# SCH_USBHubMME_2025-02-13.net
KiCad netlist of a schematic drawn in EasyEDA
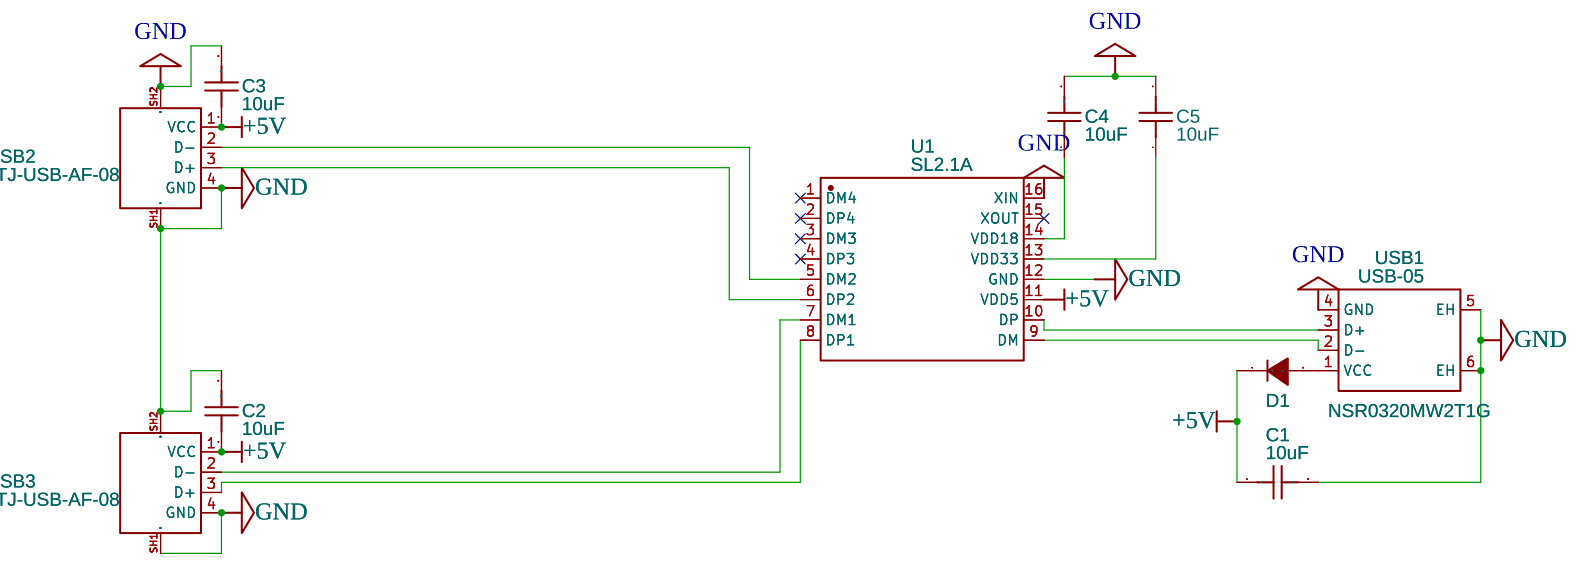
[diagram p0: schematic sheet]

(export (version "E")
  (design (tool "Eeschema 10.0.6"))
  (components
    (comp (ref "C1")
      (value "10uF")
      (fields
        (field (name "Manufacturer Part") "CL10A106KP8NNNC")
        (field (name "Manufacturer") "SAMSUNG(三星)")
      )
      (libsource (lib "") (part "CL10A106KP8NNNC"))
    )
    (comp (ref "C2")
      (value "10uF")
      (fields
        (field (name "Manufacturer Part") "CL10A106KP8NNNC")
        (field (name "Manufacturer") "SAMSUNG(三星)")
      )
      (libsource (lib "") (part "CL10A106KP8NNNC_1"))
    )
    (comp (ref "C3")
      (value "10uF")
      (fields
        (field (name "Manufacturer Part") "CL10A106KP8NNNC")
        (field (name "Manufacturer") "SAMSUNG(三星)")
      )
      (libsource (lib "") (part "CL10A106KP8NNNC_1"))
    )
    (comp (ref "C4")
      (value "10uF")
      (fields
        (field (name "Manufacturer Part") "CL10A106KP8NNNC")
        (field (name "Manufacturer") "SAMSUNG(三星)")
      )
      (libsource (lib "") (part "CL10A106KP8NNNC_1"))
    )
    (comp (ref "C5")
      (value "10uF")
      (fields
        (field (name "Manufacturer Part") "CL10A106KP8NNNC")
        (field (name "Manufacturer") "SAMSUNG(三星)")
      )
      (libsource (lib "") (part "CL10A106KP8NNNC_1"))
    )
    (comp (ref "D1")
      (value "NSR0320MW2T1G")
      (fields (field (name "Manufacturer") "onsemi(安森美)"))
      (libsource (lib "") (part "NSR0320MW2T1G"))
    )
    (comp (ref "U1")
      (value "SL2.1A")
      (fields (field (name "Manufacturer") "CoreChips(和芯润德)"))
      (libsource (lib "") (part "SL2.1A"))
    )
    (comp (ref "USB1")
      (value "USB-05")
      (fields (field (name "Manufacturer") "SOFNG(硕方)"))
      (libsource (lib "") (part "USB-05"))
    )
    (comp (ref "USB2")
      (value "JTJ-USB-AF-08")
      (fields (field (name "Manufacturer Part") "902-131A1011D10100") (field (name "Manufacturer") "精拓金"))
      (libsource (lib "") (part "JTJ-USB-AF-08"))
    )
    (comp (ref "USB3")
      (value "JTJ-USB-AF-08")
      (fields (field (name "Manufacturer Part") "902-131A1011D10100") (field (name "Manufacturer") "精拓金"))
      (libsource (lib "") (part "JTJ-USB-AF-08"))
    )
  )
  (nets
    (net (code "1") (name "+5V") (class "Default")
      (node (ref "C1") (pin "1") (pinfunction "1_1") (pintype "unspecified"))
      (node (ref "C2") (pin "1") (pinfunction "1_1") (pintype "unspecified"))
      (node (ref "C3") (pin "1") (pinfunction "1_1") (pintype "unspecified"))
      (node (ref "D1") (pin "1") (pinfunction "C_1") (pintype "unspecified"))
      (node (ref "U1") (pin "11") (pinfunction "VDD5_11") (pintype "unspecified"))
      (node (ref "USB2") (pin "1") (pinfunction "VCC_1") (pintype "input"))
      (node (ref "USB3") (pin "1") (pinfunction "VCC_1") (pintype "input"))
    )
    (net (code "2") (name "GND") (class "Default")
      (node (ref "C1") (pin "2") (pinfunction "2_2") (pintype "unspecified"))
      (node (ref "C2") (pin "2") (pinfunction "2_2") (pintype "unspecified"))
      (node (ref "C3") (pin "2") (pinfunction "2_2") (pintype "unspecified"))
      (node (ref "C4") (pin "2") (pinfunction "2_2") (pintype "unspecified"))
      (node (ref "C5") (pin "2") (pinfunction "2_2") (pintype "unspecified"))
      (node (ref "U1") (pin "12") (pinfunction "GND_12") (pintype "unspecified"))
      (node (ref "U1") (pin "16") (pinfunction "XIN_16") (pintype "unspecified"))
      (node (ref "USB1") (pin "4") (pinfunction "GND_4") (pintype "input"))
      (node (ref "USB1") (pin "5") (pinfunction "EH_5") (pintype "unspecified"))
      (node (ref "USB1") (pin "6") (pinfunction "EH_6") (pintype "unspecified"))
      (node (ref "USB2") (pin "4") (pinfunction "GND_4") (pintype "input"))
      (node (ref "USB2") (pin "SH1") (pinfunction "SH1_SH1") (pintype "unspecified"))
      (node (ref "USB2") (pin "SH2") (pinfunction "SH2_SH2") (pintype "unspecified"))
      (node (ref "USB3") (pin "4") (pinfunction "GND_4") (pintype "input"))
      (node (ref "USB3") (pin "SH1") (pinfunction "SH1_SH1") (pintype "unspecified"))
      (node (ref "USB3") (pin "SH2") (pinfunction "SH2_SH2") (pintype "unspecified"))
    )
    (net (code "3") (name "Net-(D1-A)") (class "Default")
      (node (ref "D1") (pin "2") (pinfunction "A_2") (pintype "unspecified"))
      (node (ref "USB1") (pin "1") (pinfunction "VCC_1") (pintype "input"))
    )
    (net (code "4") (name "Net-(U1-DM)") (class "Default")
      (node (ref "U1") (pin "9") (pinfunction "DM_9") (pintype "unspecified"))
      (node (ref "USB1") (pin "2") (pinfunction "D-_2") (pintype "input"))
    )
    (net (code "5") (name "Net-(U1-DM1)") (class "Default")
      (node (ref "U1") (pin "7") (pinfunction "DM1_7") (pintype "unspecified"))
      (node (ref "USB3") (pin "2") (pinfunction "D-_2") (pintype "input"))
    )
    (net (code "6") (name "Net-(U1-DM2)") (class "Default")
      (node (ref "U1") (pin "5") (pinfunction "DM2_5") (pintype "unspecified"))
      (node (ref "USB2") (pin "2") (pinfunction "D-_2") (pintype "input"))
    )
    (net (code "7") (name "Net-(U1-DP)") (class "Default")
      (node (ref "U1") (pin "10") (pinfunction "DP_10") (pintype "unspecified"))
      (node (ref "USB1") (pin "3") (pinfunction "D+_3") (pintype "input"))
    )
    (net (code "8") (name "Net-(U1-DP1)") (class "Default")
      (node (ref "U1") (pin "8") (pinfunction "DP1_8") (pintype "unspecified"))
      (node (ref "USB3") (pin "3") (pinfunction "D+_3") (pintype "input"))
    )
    (net (code "9") (name "Net-(U1-DP2)") (class "Default")
      (node (ref "U1") (pin "6") (pinfunction "DP2_6") (pintype "unspecified"))
      (node (ref "USB2") (pin "3") (pinfunction "D+_3") (pintype "input"))
    )
    (net (code "10") (name "Net-(U1-VDD18)") (class "Default")
      (node (ref "C4") (pin "1") (pinfunction "1_1") (pintype "unspecified"))
      (node (ref "U1") (pin "14") (pinfunction "VDD18_14") (pintype "unspecified"))
    )
    (net (code "11") (name "Net-(U1-VDD33)") (class "Default")
      (node (ref "C5") (pin "1") (pinfunction "1_1") (pintype "unspecified"))
      (node (ref "U1") (pin "13") (pinfunction "VDD33_13") (pintype "unspecified"))
    )
    (net (code "12") (name "unconnected-(U1-DM3-Pad3)") (class "Default")
      (node (ref "U1") (pin "3") (pinfunction "DM3_3") (pintype "unspecified+no_connect"))
    )
    (net (code "13") (name "unconnected-(U1-DM4-Pad1)") (class "Default")
      (node (ref "U1") (pin "1") (pinfunction "DM4_1") (pintype "unspecified+no_connect"))
    )
    (net (code "14") (name "unconnected-(U1-DP3-Pad4)") (class "Default")
      (node (ref "U1") (pin "4") (pinfunction "DP3_4") (pintype "unspecified+no_connect"))
    )
    (net (code "15") (name "unconnected-(U1-DP4-Pad2)") (class "Default")
      (node (ref "U1") (pin "2") (pinfunction "DP4_2") (pintype "unspecified+no_connect"))
    )
    (net (code "16") (name "unconnected-(U1-XOUT-Pad15)") (class "Default")
      (node (ref "U1") (pin "15") (pinfunction "XOUT_15") (pintype "unspecified+no_connect"))
    )
  )
)
